# tl494-orig.net
KiCad netlist of a schematic drawn in EAGLE
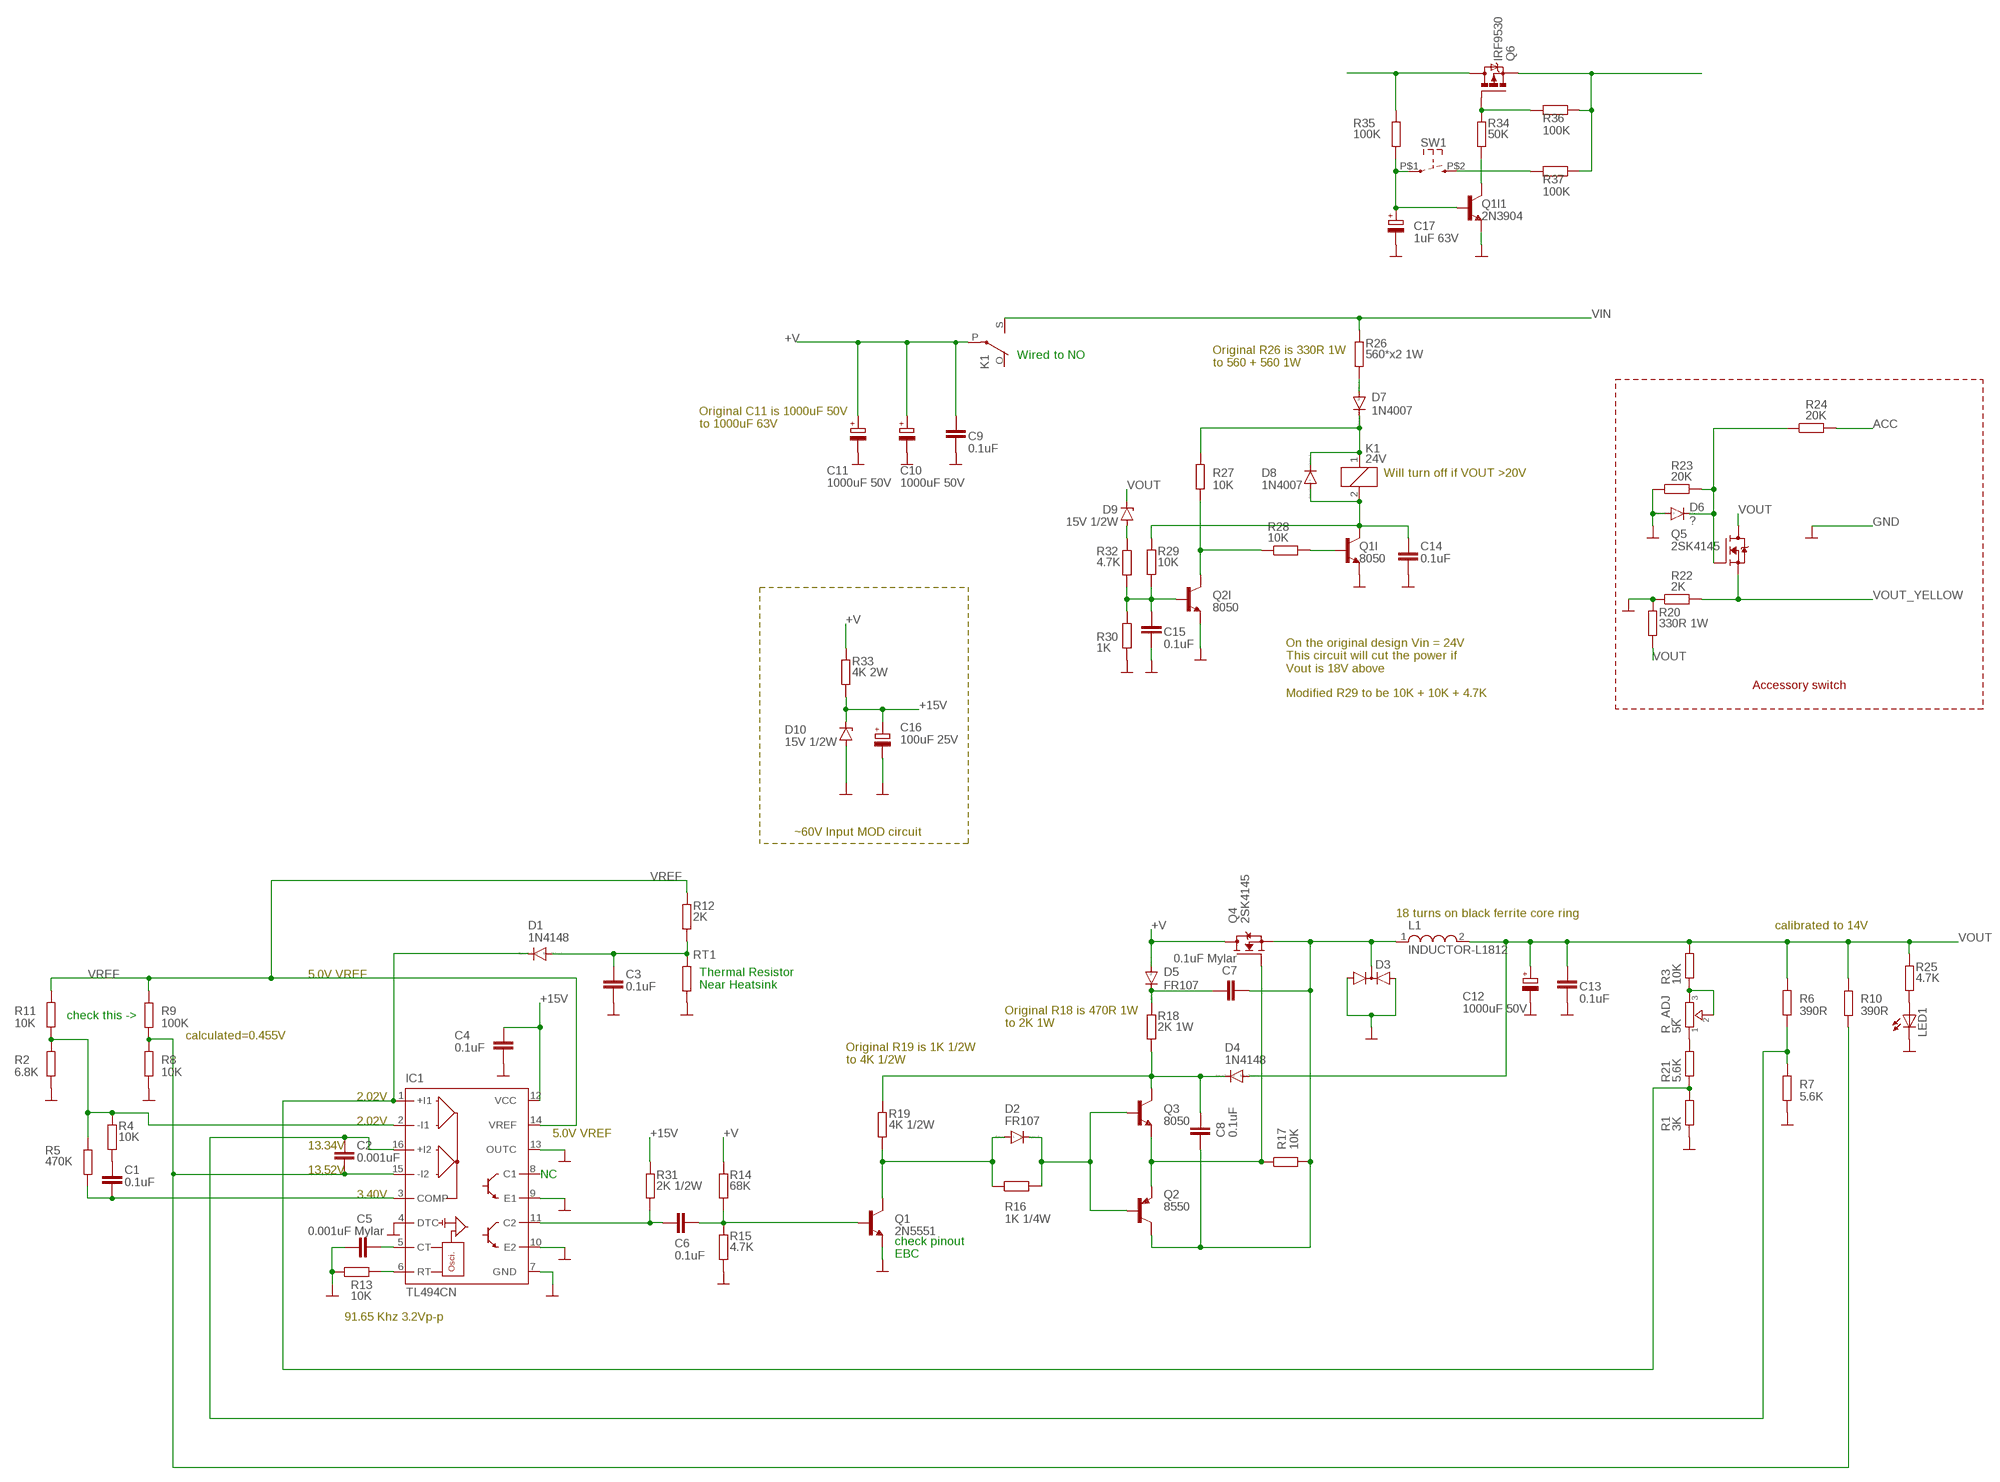
[diagram p0: schematic, sheet 1]

(export (version "E")
  (design (tool "Eeschema 10.0.6"))
  (components
    (comp (ref "C1")
      (value "0.1uF")
      (footprint "eagle-import:C050-024X044")
      (libsource (lib "eagle-import") (part "C-EU050-024X044"))
    )
    (comp (ref "C2")
      (value "0.001uF")
      (footprint "eagle-import:C050-024X044")
      (libsource (lib "eagle-import") (part "C-EU050-024X044"))
    )
    (comp (ref "C3")
      (value "0.1uF")
      (footprint "eagle-import:C050-024X044")
      (libsource (lib "eagle-import") (part "C-EU050-024X044"))
    )
    (comp (ref "C4")
      (value "0.1uF")
      (footprint "eagle-import:C050-024X044")
      (libsource (lib "eagle-import") (part "C-EU050-024X044"))
    )
    (comp (ref "C5")
      (value "0.001uF Mylar")
      (footprint "eagle-import:C050-024X044")
      (libsource (lib "eagle-import") (part "C-EU050-024X044"))
    )
    (comp (ref "C6")
      (value "0.1uF")
      (footprint "eagle-import:C050-024X044")
      (libsource (lib "eagle-import") (part "C-EU050-024X044"))
    )
    (comp (ref "C7")
      (value "0.1uF Mylar")
      (footprint "eagle-import:C050-050X075")
      (libsource (lib "eagle-import") (part "C-EU050-050X075"))
    )
    (comp (ref "C8")
      (value "0.1uF")
      (footprint "eagle-import:C050-024X044")
      (libsource (lib "eagle-import") (part "C-EU050-024X044"))
    )
    (comp (ref "C9")
      (value "0.1uF")
      (footprint "eagle-import:C050-024X044")
      (libsource (lib "eagle-import") (part "C-EU050-024X044"))
    )
    (comp (ref "C10")
      (value "1000uF 50V")
      (footprint "eagle-import:E3,5-10")
      (libsource (lib "eagle-import") (part "CPOL-EUE3.5-10"))
    )
    (comp (ref "C11")
      (value "1000uF 50V")
      (footprint "eagle-import:E3,5-10")
      (libsource (lib "eagle-import") (part "CPOL-EUE3.5-10"))
    )
    (comp (ref "C12")
      (value "1000uF 50V")
      (footprint "eagle-import:E3,5-10")
      (libsource (lib "eagle-import") (part "CPOL-EUE3.5-10"))
    )
    (comp (ref "C13")
      (value "0.1uF")
      (footprint "eagle-import:C050-024X044")
      (libsource (lib "eagle-import") (part "C-EU050-024X044"))
    )
    (comp (ref "C14")
      (value "0.1uF")
      (footprint "eagle-import:C050-024X044")
      (libsource (lib "eagle-import") (part "C-EU050-024X044"))
    )
    (comp (ref "C15")
      (value "0.1uF")
      (footprint "eagle-import:C050-024X044")
      (libsource (lib "eagle-import") (part "C-EU050-024X044"))
    )
    (comp (ref "C16")
      (value "100uF 25V")
      (footprint "eagle-import:E2,5-7")
      (libsource (lib "eagle-import") (part "CPOL-EUE2.5-7"))
    )
    (comp (ref "C17")
      (value "1uF 63V")
      (footprint "eagle-import:E3,5-10")
      (libsource (lib "eagle-import") (part "CPOL-EUE3.5-10"))
    )
    (comp (ref "D1")
      (value "1N4148")
      (footprint "eagle-import:DO35-10")
      (libsource (lib "eagle-import") (part "1N4148DO35-10"))
    )
    (comp (ref "D2")
      (value "FR107")
      (footprint "eagle-import:DO41-10")
      (libsource (lib "eagle-import") (part "1N4933"))
    )
    (comp (ref "D3")
      (value "DIODE-2AC|CATO220V")
      (footprint "eagle-import:TO220ABS")
      (libsource (lib "eagle-import") (part "DIODE-2AC|CATO220V"))
    )
    (comp (ref "D4")
      (value "1N4148")
      (footprint "eagle-import:DO35-10")
      (libsource (lib "eagle-import") (part "1N4148DO35-10"))
    )
    (comp (ref "D5")
      (value "FR107")
      (footprint "eagle-import:DO41-10")
      (libsource (lib "eagle-import") (part "1N4933"))
    )
    (comp (ref "D6")
      (value "?")
      (footprint "eagle-import:DO35-10")
      (libsource (lib "eagle-import") (part "1N4148DO35-10"))
    )
    (comp (ref "D7")
      (value "1N4007")
      (footprint "eagle-import:DO41-10")
      (libsource (lib "eagle-import") (part "1N4933"))
    )
    (comp (ref "D8")
      (value "1N4007")
      (footprint "eagle-import:DO41-10")
      (libsource (lib "eagle-import") (part "1N4933"))
    )
    (comp (ref "D9")
      (value "15V 1/2W")
      (footprint "eagle-import:DO34Z7")
      (libsource (lib "eagle-import") (part "BZV10"))
    )
    (comp (ref "D10")
      (value "15V 1/2W")
      (footprint "eagle-import:DO34Z7")
      (libsource (lib "eagle-import") (part "BZV10"))
    )
    (comp (ref "IC1")
      (value "TL494CN")
      (footprint "eagle-import:DIL16")
      (libsource (lib "eagle-import") (part "TL494NC"))
    )
    (comp (ref "K1")
      (value "24V")
      (footprint "eagle-import:G2R")
      (libsource (lib "eagle-import") (part "G2R"))
    )
    (comp (ref "L1")
      (value "INDUCTOR-L1812")
      (footprint "eagle-import:L1812")
      (libsource (lib "eagle-import") (part "INDUCTOR-L1812"))
    )
    (comp (ref "LED1")
      (value "LED-5MM")
      (footprint "eagle-import:LED-5MM")
      (libsource (lib "eagle-import") (part "LED-5MM"))
    )
    (comp (ref "Q1")
      (value "2N5551")
      (footprint "eagle-import:TO-92")
      (libsource (lib "eagle-import") (part "TRANSISTOR_BJT_NPN-TO-92-EBC"))
    )
    (comp (ref "Q1I")
      (value "8050")
      (footprint "eagle-import:TO-92")
      (libsource (lib "eagle-import") (part "TRANSISTOR_BJT_NPN-TO-92-EBC"))
    )
    (comp (ref "Q1I1")
      (value "2N3904")
      (footprint "eagle-import:TO-92")
      (libsource (lib "eagle-import") (part "TRANSISTOR_BJT_NPN-TO-92-EBC"))
    )
    (comp (ref "Q2")
      (value "8550")
      (footprint "eagle-import:TO-92")
      (libsource (lib "eagle-import") (part "TRANSISTOR_BJT_PNP-TO-92-EBC"))
    )
    (comp (ref "Q2I")
      (value "8050")
      (footprint "eagle-import:TO-92")
      (libsource (lib "eagle-import") (part "TRANSISTOR_BJT_NPN-TO-92-EBC"))
    )
    (comp (ref "Q3")
      (value "8050")
      (footprint "eagle-import:TO-92")
      (libsource (lib "eagle-import") (part "TRANSISTOR_BJT_NPN-TO-92-EBC"))
    )
    (comp (ref "Q4")
      (value "2SK4145")
      (footprint "eagle-import:TO-220V")
      (libsource (lib "eagle-import") (part "TRANSISTOR_MOSFET-N-TO220V"))
    )
    (comp (ref "Q5")
      (value "2SK4145")
      (footprint "eagle-import:TO-220V")
      (libsource (lib "eagle-import") (part "TRANSISTOR_MOSFET-N-TO220V"))
    )
    (comp (ref "Q6")
      (value "IRF9530")
      (footprint "eagle-import:TO220BV")
      (libsource (lib "eagle-import") (part "IRF9530"))
    )
    (comp (ref "R1")
      (value "3K")
      (footprint "eagle-import:0207_10")
      (libsource (lib "eagle-import") (part "R-EU_0207/10"))
    )
    (comp (ref "R2")
      (value "6.8K")
      (footprint "eagle-import:0207_10")
      (libsource (lib "eagle-import") (part "R-EU_0207/10"))
    )
    (comp (ref "R3")
      (value "10K")
      (footprint "eagle-import:0207_10")
      (libsource (lib "eagle-import") (part "R-EU_0207/10"))
    )
    (comp (ref "R4")
      (value "10K")
      (footprint "eagle-import:0207_10")
      (libsource (lib "eagle-import") (part "R-EU_0207/10"))
    )
    (comp (ref "R5")
      (value "470K")
      (footprint "eagle-import:0207_10")
      (libsource (lib "eagle-import") (part "R-EU_0207/10"))
    )
    (comp (ref "R6")
      (value "390R")
      (footprint "eagle-import:0207_10")
      (libsource (lib "eagle-import") (part "R-EU_0207/10"))
    )
    (comp (ref "R7")
      (value "5.6K")
      (footprint "eagle-import:0207_10")
      (libsource (lib "eagle-import") (part "R-EU_0207/10"))
    )
    (comp (ref "R8")
      (value "10K")
      (footprint "eagle-import:0207_10")
      (libsource (lib "eagle-import") (part "R-EU_0207/10"))
    )
    (comp (ref "R9")
      (value "100K")
      (footprint "eagle-import:0207_10")
      (libsource (lib "eagle-import") (part "R-EU_0207/10"))
    )
    (comp (ref "R10")
      (value "390R")
      (footprint "eagle-import:0207_10")
      (libsource (lib "eagle-import") (part "R-EU_0207/10"))
    )
    (comp (ref "R11")
      (value "10K")
      (footprint "eagle-import:0207_10")
      (libsource (lib "eagle-import") (part "R-EU_0207/10"))
    )
    (comp (ref "R12")
      (value "2K")
      (footprint "eagle-import:0207_10")
      (libsource (lib "eagle-import") (part "R-EU_0207/10"))
    )
    (comp (ref "R13")
      (value "10K")
      (footprint "eagle-import:0207_2V")
      (libsource (lib "eagle-import") (part "R-EU_0207/2V"))
    )
    (comp (ref "R14")
      (value "68K")
      (footprint "eagle-import:0207_10")
      (libsource (lib "eagle-import") (part "R-EU_0207/10"))
    )
    (comp (ref "R15")
      (value "4.7K")
      (footprint "eagle-import:0207_10")
      (libsource (lib "eagle-import") (part "R-EU_0207/10"))
    )
    (comp (ref "R16")
      (value "1K 1/4W")
      (footprint "eagle-import:0207_10")
      (libsource (lib "eagle-import") (part "R-EU_0207/10"))
    )
    (comp (ref "R17")
      (value "10K")
      (footprint "eagle-import:0207_10")
      (libsource (lib "eagle-import") (part "R-EU_0207/10"))
    )
    (comp (ref "R18")
      (value "2K 1W")
      (footprint "eagle-import:0207_10")
      (libsource (lib "eagle-import") (part "R-EU_0207/10"))
    )
    (comp (ref "R19")
      (value "4K 1/2W")
      (footprint "eagle-import:0207_10")
      (libsource (lib "eagle-import") (part "R-EU_0207/10"))
    )
    (comp (ref "R20")
      (value "330R 1W")
      (footprint "eagle-import:0207_10")
      (libsource (lib "eagle-import") (part "R-EU_0207/10"))
    )
    (comp (ref "R21")
      (value "5.6K")
      (footprint "eagle-import:0207_10")
      (libsource (lib "eagle-import") (part "R-EU_0207/10"))
    )
    (comp (ref "R22")
      (value "2K")
      (footprint "eagle-import:0207_10")
      (libsource (lib "eagle-import") (part "R-EU_0207/10"))
    )
    (comp (ref "R23")
      (value "20K")
      (footprint "eagle-import:0207_10")
      (libsource (lib "eagle-import") (part "R-EU_0207/10"))
    )
    (comp (ref "R24")
      (value "20K")
      (footprint "eagle-import:0207_10")
      (libsource (lib "eagle-import") (part "R-EU_0207/10"))
    )
    (comp (ref "R25")
      (value "4.7K")
      (footprint "eagle-import:0207_10")
      (libsource (lib "eagle-import") (part "R-EU_0207/10"))
    )
    (comp (ref "R26")
      (value "560*x2 1W")
      (footprint "eagle-import:0207_10")
      (libsource (lib "eagle-import") (part "R-EU_0207/10"))
    )
    (comp (ref "R27")
      (value "10K")
      (footprint "eagle-import:0207_10")
      (libsource (lib "eagle-import") (part "R-EU_0207/10"))
    )
    (comp (ref "R28")
      (value "10K")
      (footprint "eagle-import:0207_10")
      (libsource (lib "eagle-import") (part "R-EU_0207/10"))
    )
    (comp (ref "R29")
      (value "10K")
      (footprint "eagle-import:0207_10")
      (libsource (lib "eagle-import") (part "R-EU_0207/10"))
    )
    (comp (ref "R30")
      (value "1K")
      (footprint "eagle-import:0207_10")
      (libsource (lib "eagle-import") (part "R-EU_0207/10"))
    )
    (comp (ref "R31")
      (value "2K 1/2W")
      (footprint "eagle-import:0207_10")
      (libsource (lib "eagle-import") (part "R-EU_0207/10"))
    )
    (comp (ref "R32")
      (value "4.7K")
      (footprint "eagle-import:0207_10")
      (libsource (lib "eagle-import") (part "R-EU_0207/10"))
    )
    (comp (ref "R33")
      (value "4K 2W")
      (footprint "eagle-import:0414V")
      (libsource (lib "eagle-import") (part "R-EU_0414/5V"))
    )
    (comp (ref "R34")
      (value "50K")
      (footprint "eagle-import:0207_10")
      (libsource (lib "eagle-import") (part "R-EU_0207/10"))
    )
    (comp (ref "R35")
      (value "100K")
      (footprint "eagle-import:0207_10")
      (libsource (lib "eagle-import") (part "R-EU_0207/10"))
    )
    (comp (ref "R36")
      (value "100K")
      (footprint "eagle-import:0207_10")
      (libsource (lib "eagle-import") (part "R-EU_0207/10"))
    )
    (comp (ref "R37")
      (value "100K")
      (footprint "eagle-import:0207_10")
      (libsource (lib "eagle-import") (part "R-EU_0207/10"))
    )
    (comp (ref "RT1")
      (value "R-EU_0207/2V")
      (footprint "eagle-import:0207_2V")
      (libsource (lib "eagle-import") (part "R-EU_0207/2V"))
    )
    (comp (ref "R_ADJ")
      (value "5K")
      (footprint "eagle-import:TRIMMER_3362P")
      (libsource (lib "eagle-import") (part "TRIMMER-3362P"))
    )
    (comp (ref "SW1")
      (value "SW_MEMBRANE")
      (footprint "eagle-import:SW_MEMBRANE")
      (libsource (lib "eagle-import") (part "SW_MEMBRANE"))
    )
  )
  (nets
    (net (code "1") (name "/+15V") (class "Default")
      (node (ref "C16") (pin "+") (pinfunction "+_+") (pintype "passive"))
      (node (ref "C4") (pin "2") (pinfunction "2_2") (pintype "passive"))
      (node (ref "D10") (pin "C") (pinfunction "C_C") (pintype "passive"))
      (node (ref "IC1") (pin "12") (pinfunction "VCC_12") (pintype "power_in"))
      (node (ref "R31") (pin "2") (pinfunction "2_2") (pintype "passive"))
      (node (ref "R33") (pin "1") (pinfunction "1_1") (pintype "passive"))
    )
    (net (code "2") (name "/+V") (class "Default")
      (node (ref "C10") (pin "+") (pinfunction "+_+") (pintype "passive"))
      (node (ref "C11") (pin "+") (pinfunction "+_+") (pintype "passive"))
      (node (ref "C9") (pin "1") (pinfunction "1_1") (pintype "passive"))
      (node (ref "D5") (pin "A") (pinfunction "A_A") (pintype "passive"))
      (node (ref "K1") (pin "P") (pinfunction "P_P") (pintype "passive"))
      (node (ref "Q4") (pin "2") (pinfunction "D_2") (pintype "passive"))
      (node (ref "R14") (pin "2") (pinfunction "2_2") (pintype "passive"))
      (node (ref "R33") (pin "2") (pinfunction "2_2") (pintype "passive"))
    )
    (net (code "3") (name "/ACC") (class "Default")
      (node (ref "R24") (pin "2") (pinfunction "2_2") (pintype "passive"))
    )
    (net (code "4") (name "/VIN") (class "Default")
      (node (ref "K1") (pin "S") (pinfunction "S_S") (pintype "passive"))
      (node (ref "R26") (pin "2") (pinfunction "2_2") (pintype "passive"))
    )
    (net (code "5") (name "/VOUT") (class "Default")
      (node (ref "C12") (pin "+") (pinfunction "+_+") (pintype "passive"))
      (node (ref "C13") (pin "1") (pinfunction "1_1") (pintype "passive"))
      (node (ref "D4") (pin "A") (pinfunction "A_A") (pintype "passive"))
      (node (ref "D9") (pin "C") (pinfunction "C_C") (pintype "passive"))
      (node (ref "L1") (pin "2") (pinfunction "2_2") (pintype "passive"))
      (node (ref "Q5") (pin "2") (pinfunction "D_2") (pintype "passive"))
      (node (ref "R10") (pin "1") (pinfunction "1_1") (pintype "passive"))
      (node (ref "R20") (pin "1") (pinfunction "1_1") (pintype "passive"))
      (node (ref "R25") (pin "2") (pinfunction "2_2") (pintype "passive"))
      (node (ref "R3") (pin "2") (pinfunction "2_2") (pintype "passive"))
      (node (ref "R6") (pin "2") (pinfunction "2_2") (pintype "passive"))
    )
    (net (code "6") (name "/VOUT_YELLOW") (class "Default")
      (node (ref "Q5") (pin "3") (pinfunction "S_3") (pintype "passive"))
      (node (ref "R22") (pin "2") (pinfunction "2_2") (pintype "passive"))
    )
    (net (code "7") (name "/VREF") (class "Default")
      (node (ref "IC1") (pin "14") (pinfunction "VREF_14") (pintype "input"))
      (node (ref "R11") (pin "2") (pinfunction "2_2") (pintype "passive"))
      (node (ref "R12") (pin "2") (pinfunction "2_2") (pintype "passive"))
      (node (ref "R9") (pin "1") (pinfunction "1_1") (pintype "passive"))
    )
    (net (code "8") (name "Net-(C1-Pad2)") (class "Default")
      (node (ref "C1") (pin "2") (pinfunction "2_2") (pintype "passive"))
      (node (ref "R4") (pin "1") (pinfunction "1_1") (pintype "passive"))
    )
    (net (code "9") (name "Net-(C3-Pad2)") (class "Default")
      (node (ref "C3") (pin "2") (pinfunction "2_2") (pintype "passive"))
      (node (ref "D1") (pin "A") (pinfunction "A_A") (pintype "passive"))
      (node (ref "R12") (pin "1") (pinfunction "1_1") (pintype "passive"))
      (node (ref "RT1") (pin "1") (pinfunction "1_1") (pintype "passive"))
    )
    (net (code "10") (name "Net-(C7-Pad1)") (class "Default")
      (node (ref "C7") (pin "1") (pinfunction "1_1") (pintype "passive"))
      (node (ref "D5") (pin "C") (pinfunction "C_C") (pintype "passive"))
      (node (ref "R18") (pin "2") (pinfunction "2_2") (pintype "passive"))
    )
    (net (code "11") (name "Net-(D7-PadA)") (class "Default")
      (node (ref "D7") (pin "A") (pinfunction "A_A") (pintype "passive"))
      (node (ref "R26") (pin "1") (pinfunction "1_1") (pintype "passive"))
    )
    (net (code "12") (name "Net-(D7-PadC)") (class "Default")
      (node (ref "D7") (pin "C") (pinfunction "C_C") (pintype "passive"))
      (node (ref "D8") (pin "C") (pinfunction "C_C") (pintype "passive"))
      (node (ref "K1") (pin "1") (pinfunction "1_1") (pintype "passive"))
      (node (ref "R27") (pin "2") (pinfunction "2_2") (pintype "passive"))
    )
    (net (code "13") (name "Net-(D9-PadA)") (class "Default")
      (node (ref "D9") (pin "A") (pinfunction "A_A") (pintype "passive"))
      (node (ref "R32") (pin "1") (pinfunction "1_1") (pintype "passive"))
    )
    (net (code "14") (name "Net-(IC1-+I1)") (class "Default")
      (node (ref "D1") (pin "C") (pinfunction "C_C") (pintype "passive"))
      (node (ref "IC1") (pin "1") (pinfunction "+I1_1") (pintype "input"))
      (node (ref "R1") (pin "2") (pinfunction "2_2") (pintype "passive"))
      (node (ref "R21") (pin "1") (pinfunction "1_1") (pintype "passive"))
    )
    (net (code "15") (name "Net-(IC1-+I2)") (class "Default")
      (node (ref "C2") (pin "2") (pinfunction "2_2") (pintype "passive"))
      (node (ref "IC1") (pin "16") (pinfunction "+I2_16") (pintype "input"))
      (node (ref "R6") (pin "1") (pinfunction "1_1") (pintype "passive"))
      (node (ref "R7") (pin "2") (pinfunction "2_2") (pintype "passive"))
    )
    (net (code "16") (name "Net-(IC1--I1)") (class "Default")
      (node (ref "IC1") (pin "2") (pinfunction "-I1_2") (pintype "input"))
      (node (ref "R11") (pin "1") (pinfunction "1_1") (pintype "passive"))
      (node (ref "R2") (pin "2") (pinfunction "2_2") (pintype "passive"))
      (node (ref "R4") (pin "2") (pinfunction "2_2") (pintype "passive"))
      (node (ref "R5") (pin "1") (pinfunction "1_1") (pintype "passive"))
    )
    (net (code "17") (name "Net-(IC1--I2)") (class "Default")
      (node (ref "C2") (pin "1") (pinfunction "1_1") (pintype "passive"))
      (node (ref "IC1") (pin "15") (pinfunction "-I2_15") (pintype "input"))
      (node (ref "R10") (pin "2") (pinfunction "2_2") (pintype "passive"))
      (node (ref "R8") (pin "2") (pinfunction "2_2") (pintype "passive"))
      (node (ref "R9") (pin "2") (pinfunction "2_2") (pintype "passive"))
    )
    (net (code "18") (name "Net-(IC1-C2)") (class "Default")
      (node (ref "C6") (pin "2") (pinfunction "2_2") (pintype "passive"))
      (node (ref "IC1") (pin "11") (pinfunction "C2_11") (pintype "passive"))
      (node (ref "R31") (pin "1") (pinfunction "1_1") (pintype "passive"))
    )
    (net (code "19") (name "Net-(IC1-COMP)") (class "Default")
      (node (ref "C1") (pin "1") (pinfunction "1_1") (pintype "passive"))
      (node (ref "IC1") (pin "3") (pinfunction "COMP_3") (pintype "passive"))
      (node (ref "R5") (pin "2") (pinfunction "2_2") (pintype "passive"))
    )
    (net (code "20") (name "Net-(IC1-CT)") (class "Default")
      (node (ref "C5") (pin "1") (pinfunction "1_1") (pintype "passive"))
      (node (ref "IC1") (pin "5") (pinfunction "CT_5") (pintype "input"))
    )
    (net (code "21") (name "Net-(IC1-RT)") (class "Default")
      (node (ref "IC1") (pin "6") (pinfunction "RT_6") (pintype "input"))
      (node (ref "R13") (pin "2") (pinfunction "2_2") (pintype "passive"))
    )
    (net (code "22") (name "Net-(LED1-PadA)") (class "Default")
      (node (ref "LED1") (pin "A") (pinfunction "A_A") (pintype "passive"))
      (node (ref "R25") (pin "1") (pinfunction "1_1") (pintype "passive"))
    )
    (net (code "23") (name "Net-(Q1-B)") (class "Default")
      (node (ref "C6") (pin "1") (pinfunction "1_1") (pintype "passive"))
      (node (ref "Q1") (pin "2") (pinfunction "B_2") (pintype "passive"))
      (node (ref "R14") (pin "1") (pinfunction "1_1") (pintype "passive"))
      (node (ref "R15") (pin "2") (pinfunction "2_2") (pintype "passive"))
    )
    (net (code "24") (name "Net-(Q1-C)") (class "Default")
      (node (ref "D2") (pin "A") (pinfunction "A_A") (pintype "passive"))
      (node (ref "Q1") (pin "3") (pinfunction "C_3") (pintype "passive"))
      (node (ref "R16") (pin "1") (pinfunction "1_1") (pintype "passive"))
      (node (ref "R19") (pin "1") (pinfunction "1_1") (pintype "passive"))
    )
    (net (code "25") (name "Net-(Q1I-B)") (class "Default")
      (node (ref "Q1I") (pin "2") (pinfunction "B_2") (pintype "passive"))
      (node (ref "R28") (pin "2") (pinfunction "2_2") (pintype "passive"))
    )
    (net (code "26") (name "Net-(Q1I-C)") (class "Default")
      (node (ref "C14") (pin "1") (pinfunction "1_1") (pintype "passive"))
      (node (ref "D8") (pin "A") (pinfunction "A_A") (pintype "passive"))
      (node (ref "K1") (pin "2") (pinfunction "2_2") (pintype "passive"))
      (node (ref "Q1I") (pin "3") (pinfunction "C_3") (pintype "passive"))
      (node (ref "R29") (pin "2") (pinfunction "2_2") (pintype "passive"))
    )
    (net (code "27") (name "Net-(Q1I1-B)") (class "Default")
      (node (ref "C17") (pin "+") (pinfunction "+_+") (pintype "passive"))
      (node (ref "Q1I1") (pin "2") (pinfunction "B_2") (pintype "passive"))
      (node (ref "R35") (pin "1") (pinfunction "1_1") (pintype "passive"))
      (node (ref "SW1") (pin "P$1") (pinfunction "1_P$1") (pintype "passive"))
    )
    (net (code "28") (name "Net-(Q1I1-C)") (class "Default")
      (node (ref "Q1I1") (pin "3") (pinfunction "C_3") (pintype "passive"))
      (node (ref "R34") (pin "1") (pinfunction "1_1") (pintype "passive"))
    )
    (net (code "29") (name "Net-(Q2-B)") (class "Default")
      (node (ref "D2") (pin "C") (pinfunction "C_C") (pintype "passive"))
      (node (ref "Q2") (pin "2") (pinfunction "B_2") (pintype "passive"))
      (node (ref "Q3") (pin "2") (pinfunction "B_2") (pintype "passive"))
      (node (ref "R16") (pin "2") (pinfunction "2_2") (pintype "passive"))
    )
    (net (code "30") (name "Net-(Q2-C)") (class "Default")
      (node (ref "C7") (pin "2") (pinfunction "2_2") (pintype "passive"))
      (node (ref "C8") (pin "2") (pinfunction "2_2") (pintype "passive"))
      (node (ref "D3") (pin "C") (pinfunction "C_C") (pintype "passive"))
      (node (ref "L1") (pin "1") (pinfunction "1_1") (pintype "passive"))
      (node (ref "Q2") (pin "3") (pinfunction "C_3") (pintype "passive"))
      (node (ref "Q4") (pin "3") (pinfunction "S_3") (pintype "passive"))
      (node (ref "R17") (pin "2") (pinfunction "2_2") (pintype "passive"))
    )
    (net (code "31") (name "Net-(Q2-E)") (class "Default")
      (node (ref "Q2") (pin "1") (pinfunction "E_1") (pintype "passive"))
      (node (ref "Q3") (pin "1") (pinfunction "E_1") (pintype "passive"))
      (node (ref "Q4") (pin "1") (pinfunction "G_1") (pintype "passive"))
      (node (ref "R17") (pin "1") (pinfunction "1_1") (pintype "passive"))
    )
    (net (code "32") (name "Net-(Q2I-B)") (class "Default")
      (node (ref "C15") (pin "1") (pinfunction "1_1") (pintype "passive"))
      (node (ref "Q2I") (pin "2") (pinfunction "B_2") (pintype "passive"))
      (node (ref "R29") (pin "1") (pinfunction "1_1") (pintype "passive"))
      (node (ref "R30") (pin "2") (pinfunction "2_2") (pintype "passive"))
      (node (ref "R32") (pin "2") (pinfunction "2_2") (pintype "passive"))
    )
    (net (code "33") (name "Net-(Q2I-C)") (class "Default")
      (node (ref "Q2I") (pin "3") (pinfunction "C_3") (pintype "passive"))
      (node (ref "R27") (pin "1") (pinfunction "1_1") (pintype "passive"))
      (node (ref "R28") (pin "1") (pinfunction "1_1") (pintype "passive"))
    )
    (net (code "34") (name "Net-(Q3-C)") (class "Default")
      (node (ref "C8") (pin "1") (pinfunction "1_1") (pintype "passive"))
      (node (ref "D4") (pin "C") (pinfunction "C_C") (pintype "passive"))
      (node (ref "Q3") (pin "3") (pinfunction "C_3") (pintype "passive"))
      (node (ref "R18") (pin "1") (pinfunction "1_1") (pintype "passive"))
      (node (ref "R19") (pin "2") (pinfunction "2_2") (pintype "passive"))
    )
    (net (code "35") (name "Net-(Q5-G)") (class "Default")
      (node (ref "D6") (pin "C") (pinfunction "C_C") (pintype "passive"))
      (node (ref "Q5") (pin "1") (pinfunction "G_1") (pintype "passive"))
      (node (ref "R23") (pin "2") (pinfunction "2_2") (pintype "passive"))
      (node (ref "R24") (pin "1") (pinfunction "1_1") (pintype "passive"))
    )
    (net (code "36") (name "Net-(Q6-PadD)") (class "Default")
      (node (ref "Q6") (pin "D") (pinfunction "D_D") (pintype "passive"))
      (node (ref "R35") (pin "2") (pinfunction "2_2") (pintype "passive"))
    )
    (net (code "37") (name "Net-(Q6-PadG)") (class "Default")
      (node (ref "Q6") (pin "G") (pinfunction "G_G") (pintype "passive"))
      (node (ref "R34") (pin "2") (pinfunction "2_2") (pintype "passive"))
      (node (ref "R36") (pin "2") (pinfunction "2_2") (pintype "passive"))
    )
    (net (code "38") (name "Net-(Q6-PadS)") (class "Default")
      (node (ref "Q6") (pin "S") (pinfunction "S_S") (pintype "passive"))
      (node (ref "R36") (pin "1") (pinfunction "1_1") (pintype "passive"))
      (node (ref "R37") (pin "1") (pinfunction "1_1") (pintype "passive"))
    )
    (net (code "39") (name "Net-(R3-Pad1)") (class "Default")
      (node (ref "R3") (pin "1") (pinfunction "1_1") (pintype "passive"))
      (node (ref "R_ADJ") (pin "2") (pinfunction "2_2") (pintype "passive"))
      (node (ref "R_ADJ") (pin "3") (pinfunction "3_3") (pintype "passive"))
    )
    (net (code "40") (name "Net-(R21-Pad2)") (class "Default")
      (node (ref "R21") (pin "2") (pinfunction "2_2") (pintype "passive"))
      (node (ref "R_ADJ") (pin "1") (pinfunction "1_1") (pintype "passive"))
    )
    (net (code "41") (name "Net-(SW1-2)") (class "Default")
      (node (ref "R37") (pin "2") (pinfunction "2_2") (pintype "passive"))
      (node (ref "SW1") (pin "P$2") (pinfunction "2_P$2") (pintype "passive"))
    )
    (net (code "42") (name "SUPPLY_GND") (class "Default")
      (node (ref "C10") (pin "-") (pinfunction "-_-") (pintype "passive"))
      (node (ref "C11") (pin "-") (pinfunction "-_-") (pintype "passive"))
      (node (ref "C12") (pin "-") (pinfunction "-_-") (pintype "passive"))
      (node (ref "C13") (pin "2") (pinfunction "2_2") (pintype "passive"))
      (node (ref "C14") (pin "2") (pinfunction "2_2") (pintype "passive"))
      (node (ref "C15") (pin "2") (pinfunction "2_2") (pintype "passive"))
      (node (ref "C16") (pin "-") (pinfunction "-_-") (pintype "passive"))
      (node (ref "C17") (pin "-") (pinfunction "-_-") (pintype "passive"))
      (node (ref "C3") (pin "1") (pinfunction "1_1") (pintype "passive"))
      (node (ref "C4") (pin "1") (pinfunction "1_1") (pintype "passive"))
      (node (ref "C5") (pin "2") (pinfunction "2_2") (pintype "passive"))
      (node (ref "C9") (pin "2") (pinfunction "2_2") (pintype "passive"))
      (node (ref "D10") (pin "A") (pinfunction "A_A") (pintype "passive"))
      (node (ref "D3") (pin "A1") (pinfunction "A1_A1") (pintype "passive"))
      (node (ref "D3") (pin "A2") (pinfunction "A2_A2") (pintype "passive"))
      (node (ref "D6") (pin "A") (pinfunction "A_A") (pintype "passive"))
      (node (ref "IC1") (pin "10") (pinfunction "E2_10") (pintype "passive"))
      (node (ref "IC1") (pin "13") (pinfunction "OUTC_13") (pintype "output"))
      (node (ref "IC1") (pin "4") (pinfunction "DTC_4") (pintype "input"))
      (node (ref "IC1") (pin "7") (pinfunction "GND_7") (pintype "power_in"))
      (node (ref "IC1") (pin "9") (pinfunction "E1_9") (pintype "passive"))
      (node (ref "LED1") (pin "K") (pinfunction "C_K") (pintype "passive"))
      (node (ref "Q1") (pin "1") (pinfunction "E_1") (pintype "passive"))
      (node (ref "Q1I") (pin "1") (pinfunction "E_1") (pintype "passive"))
      (node (ref "Q1I1") (pin "1") (pinfunction "E_1") (pintype "passive"))
      (node (ref "Q2I") (pin "1") (pinfunction "E_1") (pintype "passive"))
      (node (ref "R1") (pin "1") (pinfunction "1_1") (pintype "passive"))
      (node (ref "R13") (pin "1") (pinfunction "1_1") (pintype "passive"))
      (node (ref "R15") (pin "1") (pinfunction "1_1") (pintype "passive"))
      (node (ref "R2") (pin "1") (pinfunction "1_1") (pintype "passive"))
      (node (ref "R20") (pin "2") (pinfunction "2_2") (pintype "passive"))
      (node (ref "R22") (pin "1") (pinfunction "1_1") (pintype "passive"))
      (node (ref "R23") (pin "1") (pinfunction "1_1") (pintype "passive"))
      (node (ref "R30") (pin "1") (pinfunction "1_1") (pintype "passive"))
      (node (ref "R7") (pin "1") (pinfunction "1_1") (pintype "passive"))
      (node (ref "R8") (pin "1") (pinfunction "1_1") (pintype "passive"))
      (node (ref "RT1") (pin "2") (pinfunction "2_2") (pintype "passive"))
    )
    (net (code "43") (name "unconnected-(IC1-C1-Pad8)") (class "Default")
      (node (ref "IC1") (pin "8") (pinfunction "C1_8") (pintype "passive"))
    )
    (net (code "44") (name "unconnected-(K1-PadO)") (class "Default")
      (node (ref "K1") (pin "O") (pinfunction "O_O") (pintype "passive"))
    )
  )
)
